# max660-inverter.net
KiCad netlist of a schematic drawn in EAGLE
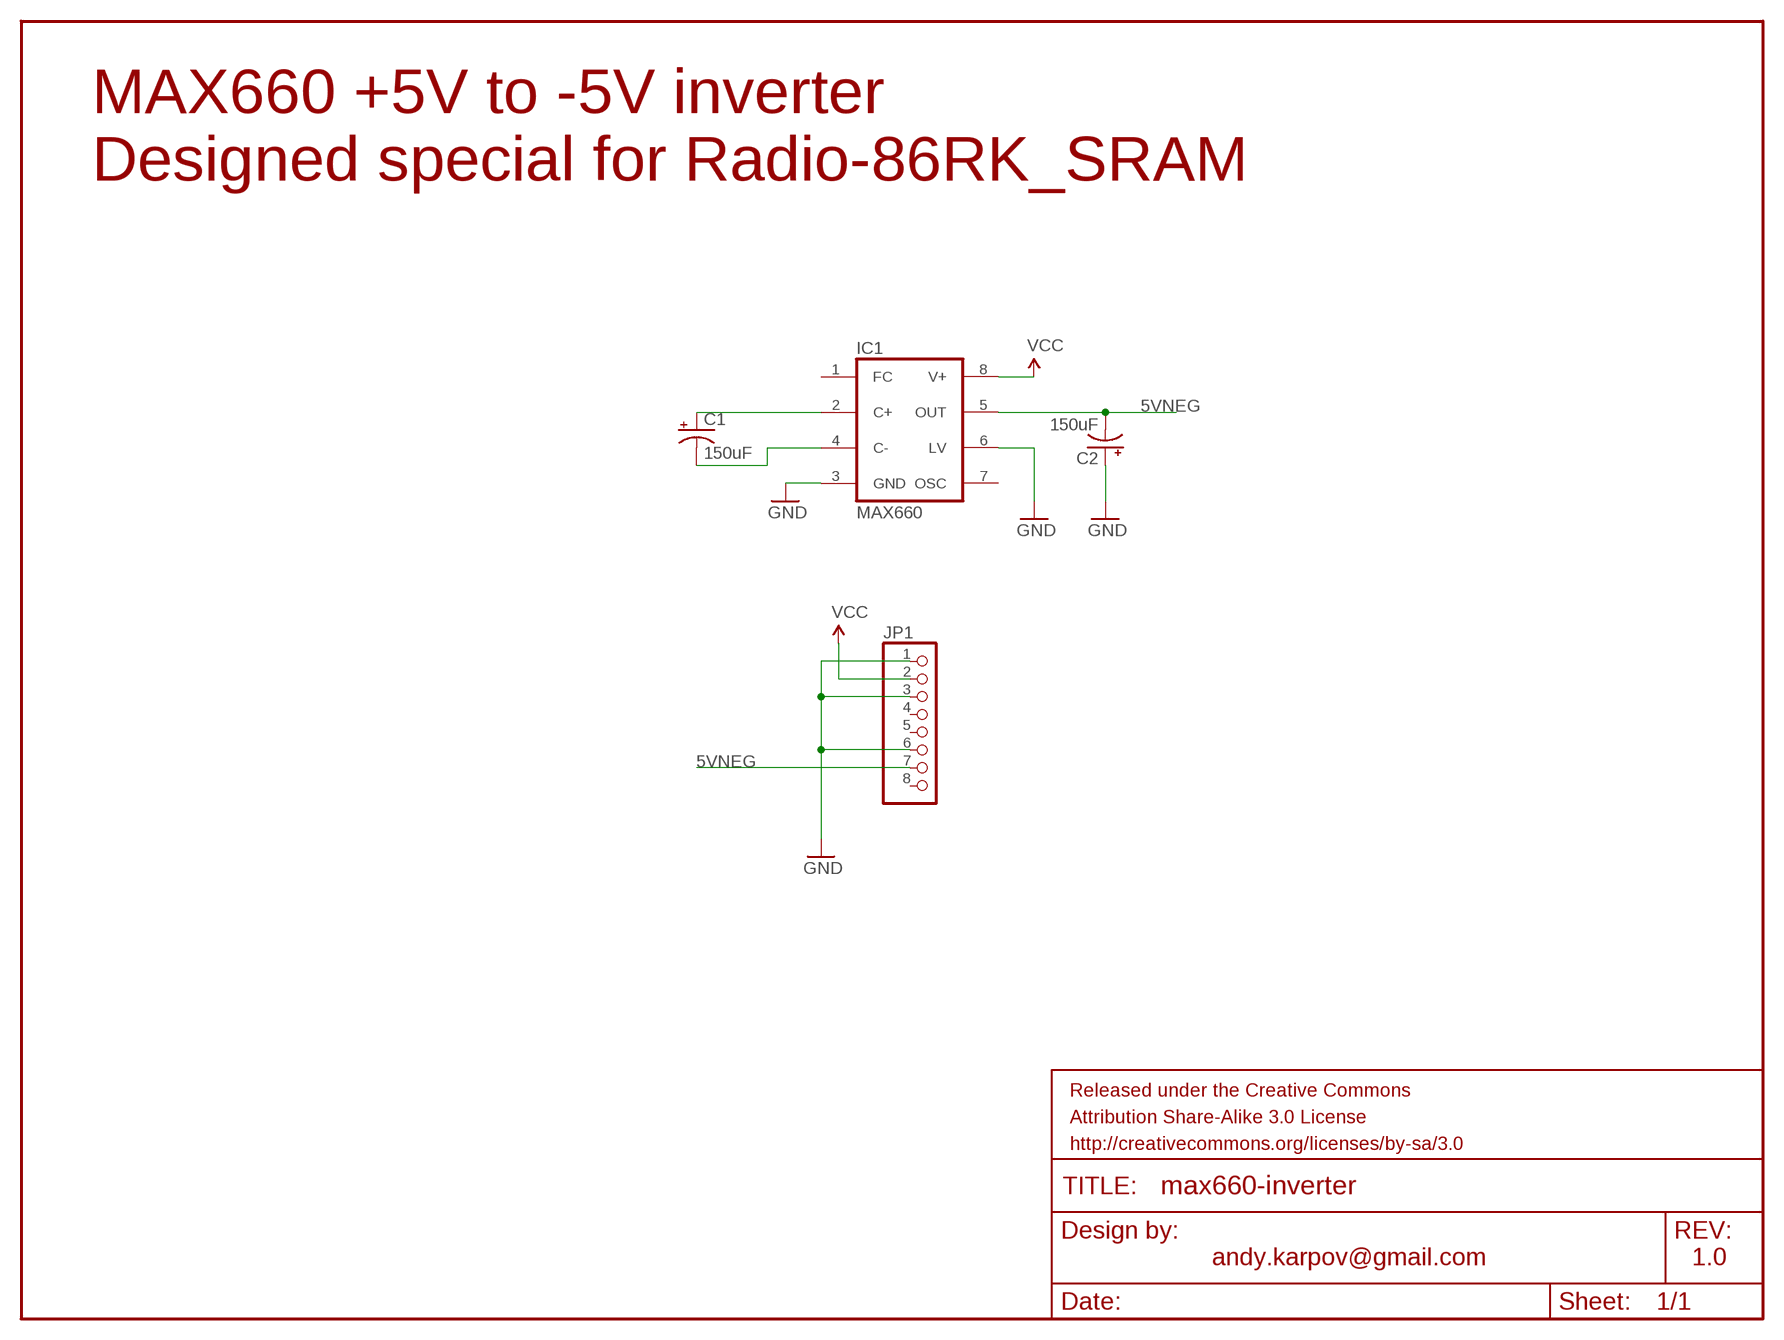
[diagram p0: schematic, sheet 1]

(export (version "E")
  (design (tool "Eeschema 10.0.6"))
  (components
    (comp (ref "C1")
      (value "150uF")
      (footprint "eagle-import:PANASONIC_D")
      (libsource (lib "eagle-import") (part "CAP_POLD"))
    )
    (comp (ref "C2")
      (value "150uF")
      (footprint "eagle-import:PANASONIC_D")
      (libsource (lib "eagle-import") (part "CAP_POLD"))
    )
    (comp (ref "FRAME1")
      (value "FRAME-LETTER")
      (footprint "eagle-import:CREATIVE_COMMONS")
      (libsource (lib "eagle-import") (part "FRAME-LETTER"))
    )
    (comp (ref "IC1")
      (value "MAX660")
      (footprint "eagle-import:SO08")
      (libsource (lib "eagle-import") (part "MAX660SAC"))
    )
    (comp (ref "JP1")
      (value "PINHD-1X8")
      (footprint "eagle-import:1X08")
      (libsource (lib "eagle-import") (part "PINHD-1X8"))
    )
  )
  (nets
    (net (code "1") (name "/5VNEG") (class "Default")
      (node (ref "C2") (pin "-") (pinfunction "-_-") (pintype "passive"))
      (node (ref "IC1") (pin "5") (pinfunction "OUT_5") (pintype "power_in"))
      (node (ref "JP1") (pin "7") (pinfunction "7_7") (pintype "passive"))
    )
    (net (code "2") (name "GND") (class "Default")
      (node (ref "C2") (pin "+") (pinfunction "+_+") (pintype "passive"))
      (node (ref "IC1") (pin "3") (pinfunction "GND_3") (pintype "power_in"))
      (node (ref "IC1") (pin "6") (pinfunction "LV_6") (pintype "passive"))
      (node (ref "JP1") (pin "1") (pinfunction "1_1") (pintype "passive"))
      (node (ref "JP1") (pin "3") (pinfunction "3_3") (pintype "passive"))
      (node (ref "JP1") (pin "6") (pinfunction "6_6") (pintype "passive"))
    )
    (net (code "3") (name "Net-(IC1-C+)") (class "Default")
      (node (ref "C1") (pin "+") (pinfunction "+_+") (pintype "passive"))
      (node (ref "IC1") (pin "2") (pinfunction "C+_2") (pintype "passive"))
    )
    (net (code "4") (name "Net-(IC1-C-)") (class "Default")
      (node (ref "C1") (pin "-") (pinfunction "-_-") (pintype "passive"))
      (node (ref "IC1") (pin "4") (pinfunction "C-_4") (pintype "passive"))
    )
    (net (code "5") (name "VCC") (class "Default")
      (node (ref "IC1") (pin "8") (pinfunction "V+_8") (pintype "power_in"))
      (node (ref "JP1") (pin "2") (pinfunction "2_2") (pintype "passive"))
    )
    (net (code "6") (name "unconnected-(IC1-FC-Pad1)") (class "Default")
      (node (ref "IC1") (pin "1") (pinfunction "FC_1") (pintype "input"))
    )
    (net (code "7") (name "unconnected-(IC1-OSC-Pad7)") (class "Default")
      (node (ref "IC1") (pin "7") (pinfunction "OSC_7") (pintype "output"))
    )
    (net (code "8") (name "unconnected-(JP1-Pad4)") (class "Default")
      (node (ref "JP1") (pin "4") (pinfunction "4_4") (pintype "passive"))
    )
    (net (code "9") (name "unconnected-(JP1-Pad5)") (class "Default")
      (node (ref "JP1") (pin "5") (pinfunction "5_5") (pintype "passive"))
    )
    (net (code "10") (name "unconnected-(JP1-Pad8)") (class "Default")
      (node (ref "JP1") (pin "8") (pinfunction "8_8") (pintype "passive"))
    )
  )
)
